# Bluetooth.net
KiCad netlist of a schematic drawn in Altium Designer
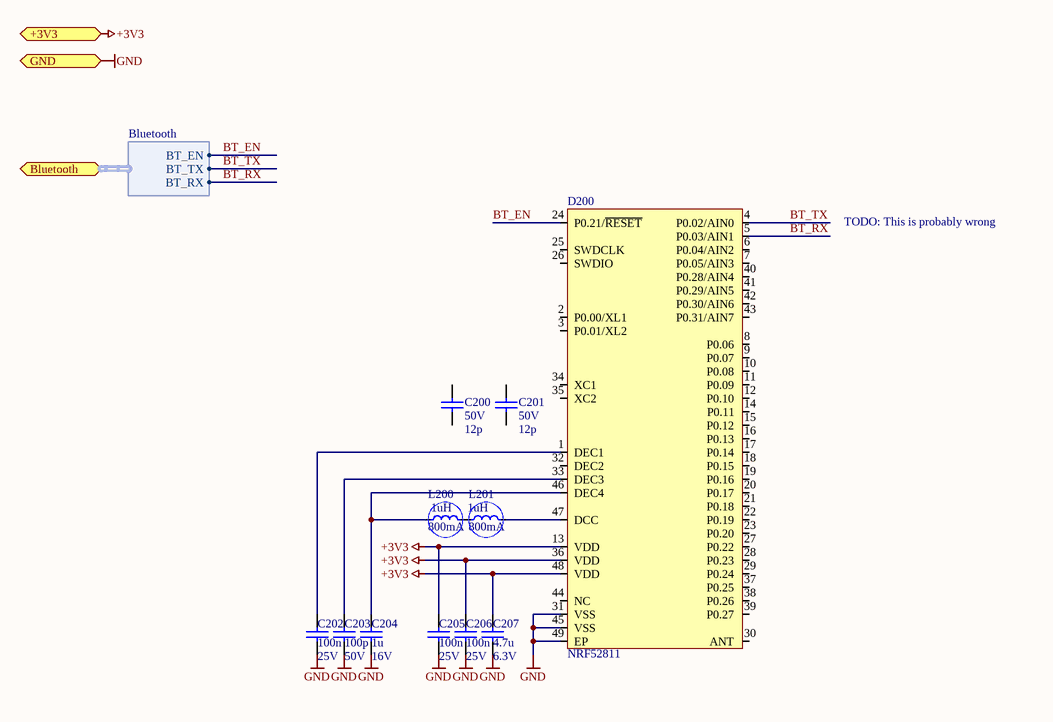
[diagram p0: Bluetooth.SchDoc]

(export (version "E")
  (design (tool "Eeschema 10.0.6"))
  (components
    (comp (ref "C200")
      (value "12p")
      (footprint "SMD_CAP_0402")
      (description "12pF ±2% 50V Ceramic Capacitor C0G, NP0 0402 (1005 Metric)")
      (fields (field (name "VALUE2") "50V") (field (name "Comment") "C_SMD_CER_12P_50V_2%_NP0_0402"))
      (libsource (lib "AM") (part "C_SMD_CER_12P_50V_2%_NP0_0402"))
    )
    (comp (ref "C201")
      (value "12p")
      (footprint "SMD_CAP_0402")
      (description "12pF ±2% 50V Ceramic Capacitor C0G, NP0 0402 (1005 Metric)")
      (fields (field (name "VALUE2") "50V") (field (name "Comment") "C_SMD_CER_12P_50V_2%_NP0_0402"))
      (libsource (lib "AM") (part "C_SMD_CER_12P_50V_2%_NP0_0402"))
    )
    (comp (ref "C202")
      (value "100n")
      (footprint "SMD_CAP_0402")
      (description "0.1µF ±10% 25V Ceramic Capacitor X7R 0402 (1005 Metric)")
      (fields (field (name "VALUE2") "25V") (field (name "Comment") "C_SMD_CER_100N_25V_10%_X7R_0402"))
      (libsource (lib "AM") (part "C_SMD_CER_100N_25V_10%_X7R_0402"))
    )
    (comp (ref "C203")
      (value "100p")
      (footprint "SMD_CAP_0402")
      (fields (field (name "VALUE2") "50V") (field (name "Comment") "C_SMD_CER_100P_50V_5%_NP0_0402"))
      (libsource (lib "AM") (part "C_SMD_CER_100P_50V_5%_NP0_0402"))
    )
    (comp (ref "C204")
      (value "1u")
      (footprint "SMD_CAP_0603")
      (description "1µF ±10% 16V Ceramic Capacitor X7R 0603 (1608 Metric)")
      (fields (field (name "VALUE2") "16V") (field (name "Comment") "C_SMD_CER_1U_16V_10%_X7R_0603"))
      (libsource (lib "AM") (part "C_SMD_CER_1U_16V_10%_X7R_0603"))
    )
    (comp (ref "C205")
      (value "100n")
      (footprint "SMD_CAP_0402")
      (description "0.1µF ±10% 25V Ceramic Capacitor X7R 0402 (1005 Metric)")
      (fields (field (name "VALUE2") "25V") (field (name "Comment") "C_SMD_CER_100N_25V_10%_X7R_0402"))
      (libsource (lib "AM") (part "C_SMD_CER_100N_25V_10%_X7R_0402"))
    )
    (comp (ref "C206")
      (value "100n")
      (footprint "SMD_CAP_0402")
      (description "0.1µF ±10% 25V Ceramic Capacitor X7R 0402 (1005 Metric)")
      (fields (field (name "VALUE2") "25V") (field (name "Comment") "C_SMD_CER_100N_25V_10%_X7R_0402"))
      (libsource (lib "AM") (part "C_SMD_CER_100N_25V_10%_X7R_0402"))
    )
    (comp (ref "C207")
      (value "4.7u")
      (footprint "SMD_CAP_0603")
      (fields (field (name "VALUE2") "6.3V") (field (name "Comment") "C_SMD_CER_4U7_6V3_10%_X5R_0603"))
      (libsource (lib "AM") (part "C_SMD_CER_4U7_6V3_10%_X5R_0603"))
    )
    (comp (ref "D200")
      (value "D_NRF52811_VQFN-48")
      (footprint "SMD_VQFN-48_0.4_EP")
      (description "IC RF TxRx + MCU Bluetooth Bluetooth v5.1 2.4GHz 48-VFQFN Exposed Pad")
      (fields (field (name "TYPE") "NRF52811"))
      (libsource (lib "AM") (part "D_NRF52811_VQFN-48"))
    )
    (comp (ref "L200")
      (value "1uH")
      (footprint "SMD_IND_1812")
      (description "SMD Coil")
      (fields (field (name "VALUE2") "800mA") (field (name "Comment") "L_SMD_AIR_SHIELD_1U_0A8_20%_1812"))
      (libsource (lib "AM") (part "L_SMD_AIR_SHIELD_1U_0A8_20%_1812"))
    )
    (comp (ref "L201")
      (value "1uH")
      (footprint "SMD_IND_1812")
      (description "SMD Coil")
      (fields (field (name "VALUE2") "800mA") (field (name "Comment") "L_SMD_AIR_SHIELD_1U_0A8_20%_1812"))
      (libsource (lib "AM") (part "L_SMD_AIR_SHIELD_1U_0A8_20%_1812"))
    )
  )
  (nets
    (net (code "2") (name "+3V3") (class "Default")
      (node (ref "C205") (pin "2") (pinfunction "2_2") (pintype "passive"))
      (node (ref "C206") (pin "2") (pinfunction "2_2") (pintype "passive"))
      (node (ref "C207") (pin "2") (pinfunction "2_2") (pintype "passive"))
      (node (ref "D200") (pin "13") (pinfunction "VDD_13") (pintype "passive"))
      (node (ref "D200") (pin "36") (pinfunction "VDD_36") (pintype "passive"))
      (node (ref "D200") (pin "48") (pinfunction "VDD_48") (pintype "passive"))
    )
    (net (code "3") (name "/BT_EN") (class "Default")
      (node (ref "D200") (pin "24") (pinfunction "P0.21/~{RESET}_24") (pintype "passive"))
    )
    (net (code "4") (name "/BT_RX") (class "Default")
      (node (ref "D200") (pin "5") (pinfunction "P0.03/AIN1_5") (pintype "passive"))
    )
    (net (code "5") (name "/BT_TX") (class "Default")
      (node (ref "D200") (pin "4") (pinfunction "P0.02/AIN0_4") (pintype "passive"))
    )
    (net (code "7") (name "GND") (class "Default")
      (node (ref "C202") (pin "1") (pinfunction "1_1") (pintype "passive"))
      (node (ref "C203") (pin "1") (pinfunction "1_1") (pintype "passive"))
      (node (ref "C204") (pin "1") (pinfunction "1_1") (pintype "passive"))
      (node (ref "C205") (pin "1") (pinfunction "1_1") (pintype "passive"))
      (node (ref "C206") (pin "1") (pinfunction "1_1") (pintype "passive"))
      (node (ref "C207") (pin "1") (pinfunction "1_1") (pintype "passive"))
      (node (ref "D200") (pin "31") (pinfunction "VSS_31") (pintype "passive"))
      (node (ref "D200") (pin "45") (pinfunction "VSS_45") (pintype "passive"))
      (node (ref "D200") (pin "49") (pinfunction "EP_49") (pintype "passive"))
    )
    (net (code "8") (name "Net-(D200-DCC)") (class "Default")
      (node (ref "D200") (pin "47") (pinfunction "DCC_47") (pintype "passive"))
      (node (ref "L201") (pin "2") (pinfunction "2_2") (pintype "passive"))
    )
    (net (code "9") (name "Net-(D200-DEC1)") (class "Default")
      (node (ref "C202") (pin "2") (pinfunction "2_2") (pintype "passive"))
      (node (ref "D200") (pin "1") (pinfunction "DEC1_1") (pintype "passive"))
    )
    (net (code "10") (name "Net-(D200-DEC3)") (class "Default")
      (node (ref "C203") (pin "2") (pinfunction "2_2") (pintype "passive"))
      (node (ref "D200") (pin "33") (pinfunction "DEC3_33") (pintype "passive"))
    )
    (net (code "11") (name "Net-(D200-DEC4)") (class "Default")
      (node (ref "C204") (pin "2") (pinfunction "2_2") (pintype "passive"))
      (node (ref "D200") (pin "46") (pinfunction "DEC4_46") (pintype "passive"))
      (node (ref "L200") (pin "1") (pinfunction "1_1") (pintype "passive"))
    )
    (net (code "12") (name "Net-(L200-Pad2)") (class "Default")
      (node (ref "L200") (pin "2") (pinfunction "2_2") (pintype "passive"))
      (node (ref "L201") (pin "1") (pinfunction "1_1") (pintype "passive"))
    )
    (net (code "13") (name "unconnected-(C200-Pad1)") (class "Default")
      (node (ref "C200") (pin "1") (pinfunction "1_1") (pintype "passive"))
    )
    (net (code "14") (name "unconnected-(C200-Pad2)") (class "Default")
      (node (ref "C200") (pin "2") (pinfunction "2_2") (pintype "passive"))
    )
    (net (code "15") (name "unconnected-(C201-Pad1)") (class "Default")
      (node (ref "C201") (pin "1") (pinfunction "1_1") (pintype "passive"))
    )
    (net (code "16") (name "unconnected-(C201-Pad2)") (class "Default")
      (node (ref "C201") (pin "2") (pinfunction "2_2") (pintype "passive"))
    )
    (net (code "17") (name "unconnected-(D200-ANT-Pad30)") (class "Default")
      (node (ref "D200") (pin "30") (pinfunction "ANT_30") (pintype "passive"))
    )
    (net (code "18") (name "unconnected-(D200-DEC2-Pad32)") (class "Default")
      (node (ref "D200") (pin "32") (pinfunction "DEC2_32") (pintype "passive"))
    )
    (net (code "19") (name "unconnected-(D200-NC-Pad44)") (class "Default")
      (node (ref "D200") (pin "44") (pinfunction "NC_44") (pintype "passive"))
    )
    (net (code "20") (name "unconnected-(D200-P0.00{slash}XL1-Pad2)") (class "Default")
      (node (ref "D200") (pin "2") (pinfunction "P0.00/XL1_2") (pintype "passive"))
    )
    (net (code "21") (name "unconnected-(D200-P0.01{slash}XL2-Pad3)") (class "Default")
      (node (ref "D200") (pin "3") (pinfunction "P0.01/XL2_3") (pintype "passive"))
    )
    (net (code "22") (name "unconnected-(D200-P0.04{slash}AIN2-Pad6)") (class "Default")
      (node (ref "D200") (pin "6") (pinfunction "P0.04/AIN2_6") (pintype "passive"))
    )
    (net (code "23") (name "unconnected-(D200-P0.05{slash}AIN3-Pad7)") (class "Default")
      (node (ref "D200") (pin "7") (pinfunction "P0.05/AIN3_7") (pintype "passive"))
    )
    (net (code "24") (name "unconnected-(D200-P0.06-Pad8)") (class "Default")
      (node (ref "D200") (pin "8") (pinfunction "P0.06_8") (pintype "passive"))
    )
    (net (code "25") (name "unconnected-(D200-P0.07-Pad9)") (class "Default")
      (node (ref "D200") (pin "9") (pinfunction "P0.07_9") (pintype "passive"))
    )
    (net (code "26") (name "unconnected-(D200-P0.08-Pad10)") (class "Default")
      (node (ref "D200") (pin "10") (pinfunction "P0.08_10") (pintype "passive"))
    )
    (net (code "27") (name "unconnected-(D200-P0.09-Pad11)") (class "Default")
      (node (ref "D200") (pin "11") (pinfunction "P0.09_11") (pintype "passive"))
    )
    (net (code "28") (name "unconnected-(D200-P0.10-Pad12)") (class "Default")
      (node (ref "D200") (pin "12") (pinfunction "P0.10_12") (pintype "passive"))
    )
    (net (code "29") (name "unconnected-(D200-P0.11-Pad14)") (class "Default")
      (node (ref "D200") (pin "14") (pinfunction "P0.11_14") (pintype "passive"))
    )
    (net (code "30") (name "unconnected-(D200-P0.12-Pad15)") (class "Default")
      (node (ref "D200") (pin "15") (pinfunction "P0.12_15") (pintype "passive"))
    )
    (net (code "31") (name "unconnected-(D200-P0.13-Pad16)") (class "Default")
      (node (ref "D200") (pin "16") (pinfunction "P0.13_16") (pintype "passive"))
    )
    (net (code "32") (name "unconnected-(D200-P0.14-Pad17)") (class "Default")
      (node (ref "D200") (pin "17") (pinfunction "P0.14_17") (pintype "passive"))
    )
    (net (code "33") (name "unconnected-(D200-P0.15-Pad18)") (class "Default")
      (node (ref "D200") (pin "18") (pinfunction "P0.15_18") (pintype "passive"))
    )
    (net (code "34") (name "unconnected-(D200-P0.16-Pad19)") (class "Default")
      (node (ref "D200") (pin "19") (pinfunction "P0.16_19") (pintype "passive"))
    )
    (net (code "35") (name "unconnected-(D200-P0.17-Pad20)") (class "Default")
      (node (ref "D200") (pin "20") (pinfunction "P0.17_20") (pintype "passive"))
    )
    (net (code "36") (name "unconnected-(D200-P0.18-Pad21)") (class "Default")
      (node (ref "D200") (pin "21") (pinfunction "P0.18_21") (pintype "passive"))
    )
    (net (code "37") (name "unconnected-(D200-P0.19-Pad22)") (class "Default")
      (node (ref "D200") (pin "22") (pinfunction "P0.19_22") (pintype "passive"))
    )
    (net (code "38") (name "unconnected-(D200-P0.20-Pad23)") (class "Default")
      (node (ref "D200") (pin "23") (pinfunction "P0.20_23") (pintype "passive"))
    )
    (net (code "39") (name "unconnected-(D200-P0.22-Pad27)") (class "Default")
      (node (ref "D200") (pin "27") (pinfunction "P0.22_27") (pintype "passive"))
    )
    (net (code "40") (name "unconnected-(D200-P0.23-Pad28)") (class "Default")
      (node (ref "D200") (pin "28") (pinfunction "P0.23_28") (pintype "passive"))
    )
    (net (code "41") (name "unconnected-(D200-P0.24-Pad29)") (class "Default")
      (node (ref "D200") (pin "29") (pinfunction "P0.24_29") (pintype "passive"))
    )
    (net (code "42") (name "unconnected-(D200-P0.25-Pad37)") (class "Default")
      (node (ref "D200") (pin "37") (pinfunction "P0.25_37") (pintype "passive"))
    )
    (net (code "43") (name "unconnected-(D200-P0.26-Pad38)") (class "Default")
      (node (ref "D200") (pin "38") (pinfunction "P0.26_38") (pintype "passive"))
    )
    (net (code "44") (name "unconnected-(D200-P0.27-Pad39)") (class "Default")
      (node (ref "D200") (pin "39") (pinfunction "P0.27_39") (pintype "passive"))
    )
    (net (code "45") (name "unconnected-(D200-P0.28{slash}AIN4-Pad40)") (class "Default")
      (node (ref "D200") (pin "40") (pinfunction "P0.28/AIN4_40") (pintype "passive"))
    )
    (net (code "46") (name "unconnected-(D200-P0.29{slash}AIN5-Pad41)") (class "Default")
      (node (ref "D200") (pin "41") (pinfunction "P0.29/AIN5_41") (pintype "passive"))
    )
    (net (code "47") (name "unconnected-(D200-P0.30{slash}AIN6-Pad42)") (class "Default")
      (node (ref "D200") (pin "42") (pinfunction "P0.30/AIN6_42") (pintype "passive"))
    )
    (net (code "48") (name "unconnected-(D200-P0.31{slash}AIN7-Pad43)") (class "Default")
      (node (ref "D200") (pin "43") (pinfunction "P0.31/AIN7_43") (pintype "passive"))
    )
    (net (code "49") (name "unconnected-(D200-SWDCLK-Pad25)") (class "Default")
      (node (ref "D200") (pin "25") (pinfunction "SWDCLK_25") (pintype "passive"))
    )
    (net (code "50") (name "unconnected-(D200-SWDIO-Pad26)") (class "Default")
      (node (ref "D200") (pin "26") (pinfunction "SWDIO_26") (pintype "passive"))
    )
    (net (code "51") (name "unconnected-(D200-XC1-Pad34)") (class "Default")
      (node (ref "D200") (pin "34") (pinfunction "XC1_34") (pintype "passive"))
    )
    (net (code "52") (name "unconnected-(D200-XC2-Pad35)") (class "Default")
      (node (ref "D200") (pin "35") (pinfunction "XC2_35") (pintype "passive"))
    )
  )
)
